# led-matrix-proto.net
KiCad netlist of a schematic drawn in EAGLE
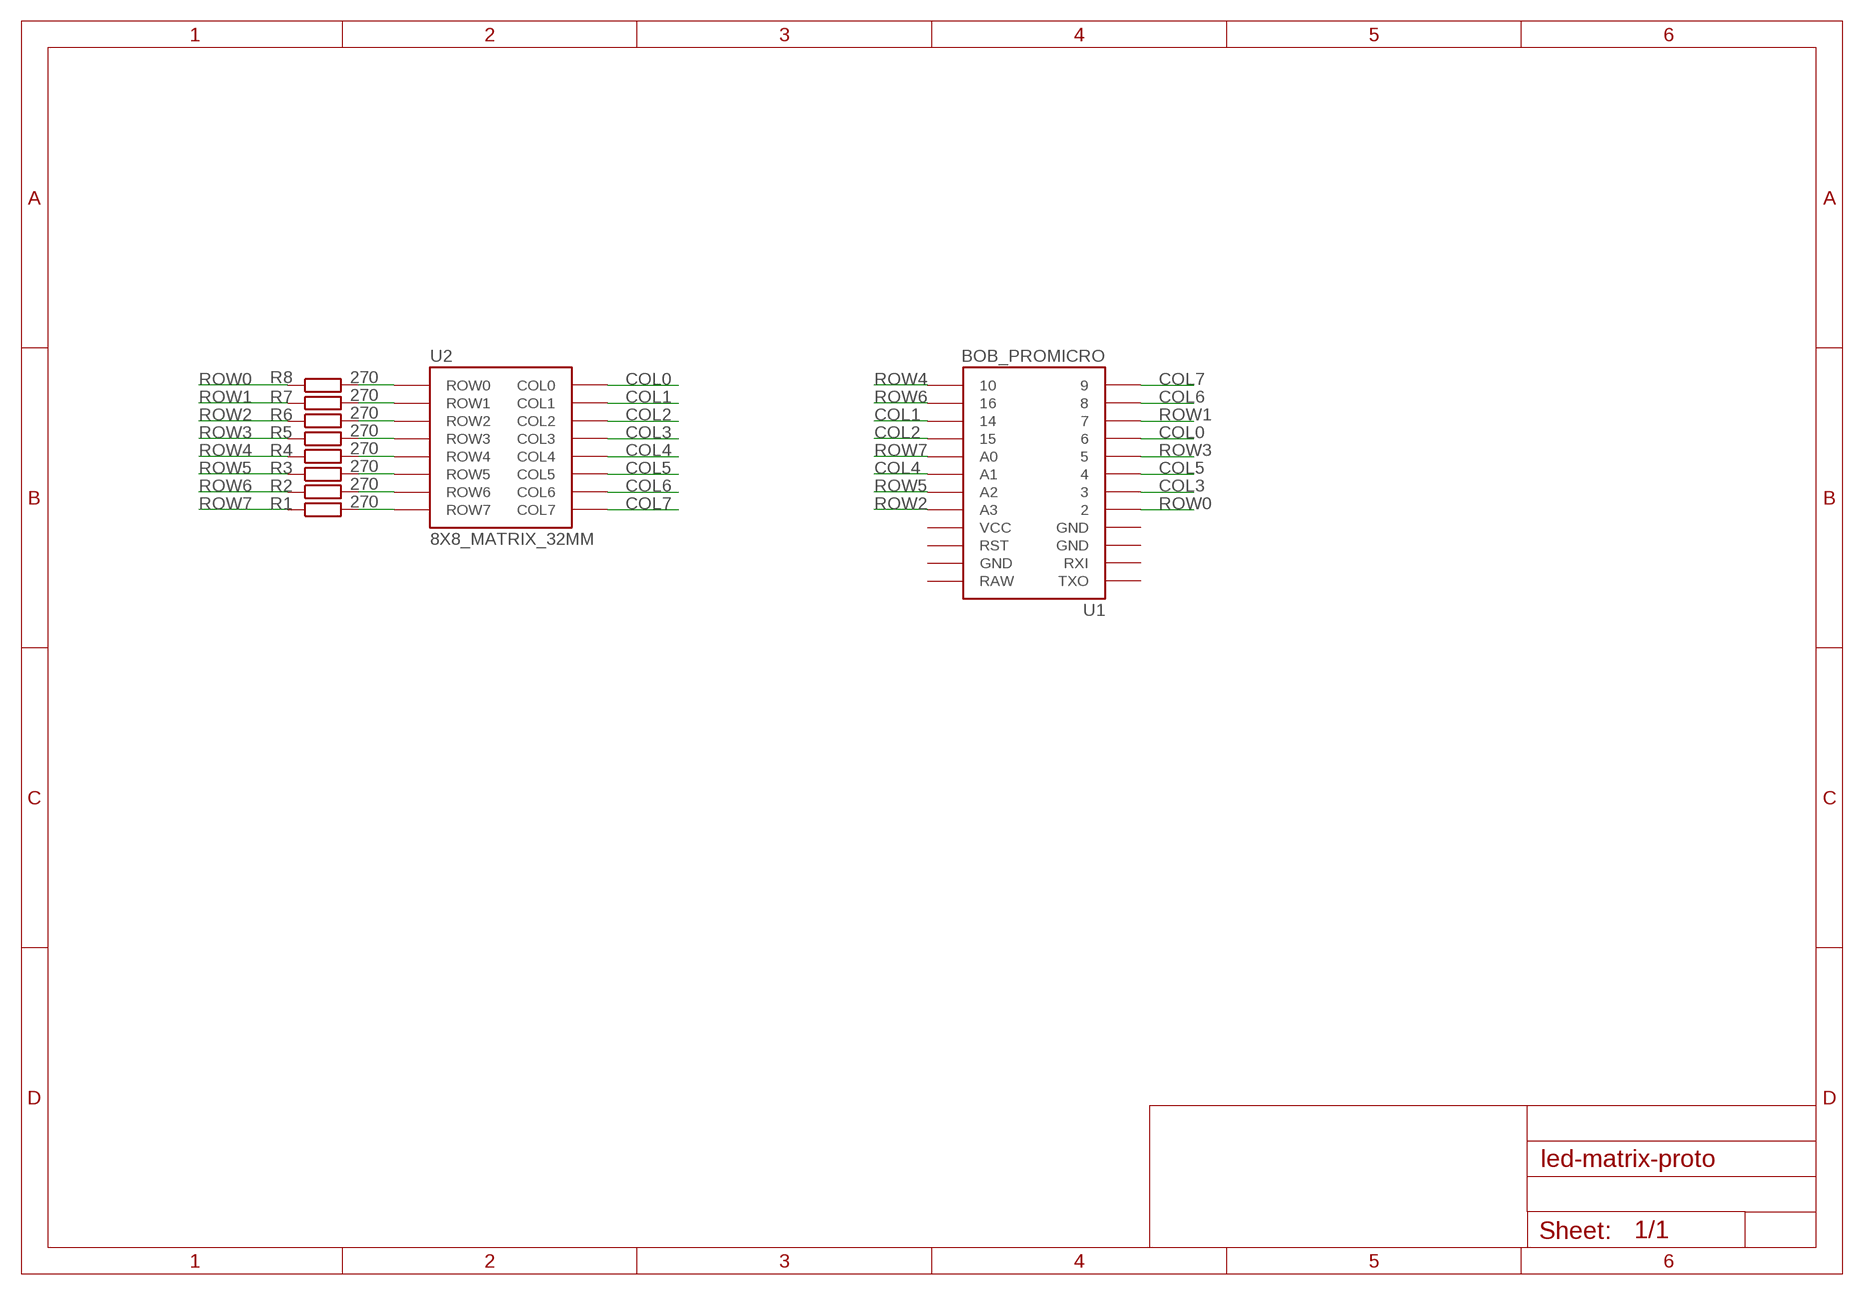
[diagram p0: schematic, sheet 1]

(export (version "E")
  (design (tool "Eeschema 10.0.6"))
  (components
    (comp (ref "R1")
      (value "270")
      (footprint "eagle-import:R0603")
      (libsource (lib "eagle-import") (part "R-EU_R0603"))
    )
    (comp (ref "R2")
      (value "270")
      (footprint "eagle-import:R0603")
      (libsource (lib "eagle-import") (part "R-EU_R0603"))
    )
    (comp (ref "R3")
      (value "270")
      (footprint "eagle-import:R0603")
      (libsource (lib "eagle-import") (part "R-EU_R0603"))
    )
    (comp (ref "R4")
      (value "270")
      (footprint "eagle-import:R0603")
      (libsource (lib "eagle-import") (part "R-EU_R0603"))
    )
    (comp (ref "R5")
      (value "270")
      (footprint "eagle-import:R0603")
      (libsource (lib "eagle-import") (part "R-EU_R0603"))
    )
    (comp (ref "R6")
      (value "270")
      (footprint "eagle-import:R0603")
      (libsource (lib "eagle-import") (part "R-EU_R0603"))
    )
    (comp (ref "R7")
      (value "270")
      (footprint "eagle-import:R0603")
      (libsource (lib "eagle-import") (part "R-EU_R0603"))
    )
    (comp (ref "R8")
      (value "270")
      (footprint "eagle-import:R0603")
      (libsource (lib "eagle-import") (part "R-EU_R0603"))
    )
    (comp (ref "U1")
      (value "BOB_PROMICRO")
      (footprint "eagle-import:BOB_PROMICRO")
      (libsource (lib "eagle-import") (part "BOB_PROMICRO"))
    )
    (comp (ref "U2")
      (value "8X8_MATRIX_32MM")
      (footprint "eagle-import:8X8_MATRIX_32MM")
      (libsource (lib "eagle-import") (part "8X8_MATRIX_32MM"))
    )
  )
  (nets
    (net (code "1") (name "/COL0") (class "Default")
      (node (ref "U1") (pin "6") (pinfunction "6_6") (pintype "bidirectional"))
      (node (ref "U2") (pin "4") (pinfunction "COL0_4") (pintype "bidirectional"))
    )
    (net (code "2") (name "/COL1") (class "Default")
      (node (ref "U1") (pin "14") (pinfunction "14_14") (pintype "bidirectional"))
      (node (ref "U2") (pin "14") (pinfunction "COL1_14") (pintype "bidirectional"))
    )
    (net (code "3") (name "/COL2") (class "Default")
      (node (ref "U1") (pin "15") (pinfunction "15_15") (pintype "bidirectional"))
      (node (ref "U2") (pin "13") (pinfunction "COL2_13") (pintype "bidirectional"))
    )
    (net (code "4") (name "/COL3") (class "Default")
      (node (ref "U1") (pin "3") (pinfunction "3_3") (pintype "bidirectional"))
      (node (ref "U2") (pin "7") (pinfunction "COL3_7") (pintype "bidirectional"))
    )
    (net (code "5") (name "/COL4") (class "Default")
      (node (ref "U1") (pin "A1") (pinfunction "A1_A1") (pintype "bidirectional"))
      (node (ref "U2") (pin "11") (pinfunction "COL4_11") (pintype "bidirectional"))
    )
    (net (code "6") (name "/COL5") (class "Default")
      (node (ref "U1") (pin "4") (pinfunction "4_4") (pintype "bidirectional"))
      (node (ref "U2") (pin "6") (pinfunction "COL5_6") (pintype "bidirectional"))
    )
    (net (code "7") (name "/COL6") (class "Default")
      (node (ref "U1") (pin "8") (pinfunction "8_8") (pintype "bidirectional"))
      (node (ref "U2") (pin "2") (pinfunction "COL6_2") (pintype "bidirectional"))
    )
    (net (code "8") (name "/COL7") (class "Default")
      (node (ref "U1") (pin "9") (pinfunction "9_9") (pintype "bidirectional"))
      (node (ref "U2") (pin "1") (pinfunction "COL7_1") (pintype "bidirectional"))
    )
    (net (code "9") (name "/ROW0") (class "Default")
      (node (ref "R8") (pin "1") (pinfunction "1_1") (pintype "passive"))
      (node (ref "U1") (pin "2") (pinfunction "2_2") (pintype "bidirectional"))
    )
    (net (code "10") (name "/ROW1") (class "Default")
      (node (ref "R7") (pin "1") (pinfunction "1_1") (pintype "passive"))
      (node (ref "U1") (pin "7") (pinfunction "7_7") (pintype "bidirectional"))
    )
    (net (code "11") (name "/ROW2") (class "Default")
      (node (ref "R6") (pin "1") (pinfunction "1_1") (pintype "passive"))
      (node (ref "U1") (pin "A3") (pinfunction "A3_A3") (pintype "bidirectional"))
    )
    (net (code "12") (name "/ROW3") (class "Default")
      (node (ref "R5") (pin "1") (pinfunction "1_1") (pintype "passive"))
      (node (ref "U1") (pin "5") (pinfunction "5_5") (pintype "bidirectional"))
    )
    (net (code "13") (name "/ROW4") (class "Default")
      (node (ref "R4") (pin "1") (pinfunction "1_1") (pintype "passive"))
      (node (ref "U1") (pin "10") (pinfunction "10_10") (pintype "bidirectional"))
    )
    (net (code "14") (name "/ROW5") (class "Default")
      (node (ref "R3") (pin "1") (pinfunction "1_1") (pintype "passive"))
      (node (ref "U1") (pin "A2") (pinfunction "A2_A2") (pintype "bidirectional"))
    )
    (net (code "15") (name "/ROW6") (class "Default")
      (node (ref "R2") (pin "1") (pinfunction "1_1") (pintype "passive"))
      (node (ref "U1") (pin "16") (pinfunction "16_16") (pintype "bidirectional"))
    )
    (net (code "16") (name "/ROW7") (class "Default")
      (node (ref "R1") (pin "1") (pinfunction "1_1") (pintype "passive"))
      (node (ref "U1") (pin "A0") (pinfunction "A0_A0") (pintype "bidirectional"))
    )
    (net (code "17") (name "Net-(U2-ROW0)") (class "Default")
      (node (ref "R8") (pin "2") (pinfunction "2_2") (pintype "passive"))
      (node (ref "U2") (pin "8") (pinfunction "ROW0_8") (pintype "bidirectional"))
    )
    (net (code "18") (name "Net-(U2-ROW1)") (class "Default")
      (node (ref "R7") (pin "2") (pinfunction "2_2") (pintype "passive"))
      (node (ref "U2") (pin "3") (pinfunction "ROW1_3") (pintype "bidirectional"))
    )
    (net (code "19") (name "Net-(U2-ROW2)") (class "Default")
      (node (ref "R6") (pin "2") (pinfunction "2_2") (pintype "passive"))
      (node (ref "U2") (pin "9") (pinfunction "ROW2_9") (pintype "bidirectional"))
    )
    (net (code "20") (name "Net-(U2-ROW3)") (class "Default")
      (node (ref "R5") (pin "2") (pinfunction "2_2") (pintype "passive"))
      (node (ref "U2") (pin "5") (pinfunction "ROW3_5") (pintype "bidirectional"))
    )
    (net (code "21") (name "Net-(U2-ROW4)") (class "Default")
      (node (ref "R4") (pin "2") (pinfunction "2_2") (pintype "passive"))
      (node (ref "U2") (pin "16") (pinfunction "ROW4_16") (pintype "bidirectional"))
    )
    (net (code "22") (name "Net-(U2-ROW5)") (class "Default")
      (node (ref "R3") (pin "2") (pinfunction "2_2") (pintype "passive"))
      (node (ref "U2") (pin "10") (pinfunction "ROW5_10") (pintype "bidirectional"))
    )
    (net (code "23") (name "Net-(U2-ROW6)") (class "Default")
      (node (ref "R2") (pin "2") (pinfunction "2_2") (pintype "passive"))
      (node (ref "U2") (pin "15") (pinfunction "ROW6_15") (pintype "bidirectional"))
    )
    (net (code "24") (name "Net-(U2-ROW7)") (class "Default")
      (node (ref "R1") (pin "2") (pinfunction "2_2") (pintype "passive"))
      (node (ref "U2") (pin "12") (pinfunction "ROW7_12") (pintype "bidirectional"))
    )
    (net (code "25") (name "unconnected-(U1-GND-PadGND@1)") (class "Default")
      (node (ref "U1") (pin "GND@1") (pinfunction "GND_GND@1") (pintype "bidirectional"))
    )
    (net (code "26") (name "unconnected-(U1-GND-PadGND@2)") (class "Default")
      (node (ref "U1") (pin "GND@2") (pinfunction "GND_GND@2") (pintype "bidirectional"))
    )
    (net (code "27") (name "unconnected-(U1-GND-PadGND@3)") (class "Default")
      (node (ref "U1") (pin "GND@3") (pinfunction "GND_GND@3") (pintype "bidirectional"))
    )
    (net (code "28") (name "unconnected-(U1-PadRAW)") (class "Default")
      (node (ref "U1") (pin "RAW") (pinfunction "RAW_RAW") (pintype "bidirectional"))
    )
    (net (code "29") (name "unconnected-(U1-PadRST)") (class "Default")
      (node (ref "U1") (pin "RST") (pinfunction "RST_RST") (pintype "bidirectional"))
    )
    (net (code "30") (name "unconnected-(U1-PadRXI)") (class "Default")
      (node (ref "U1") (pin "RXI") (pinfunction "RXI_RXI") (pintype "bidirectional"))
    )
    (net (code "31") (name "unconnected-(U1-PadTXO)") (class "Default")
      (node (ref "U1") (pin "TXO") (pinfunction "TXO_TXO") (pintype "bidirectional"))
    )
    (net (code "32") (name "unconnected-(U1-PadVCC)") (class "Default")
      (node (ref "U1") (pin "VCC") (pinfunction "VCC_VCC") (pintype "bidirectional"))
    )
  )
)
